# LED_aluminum.net
KiCad netlist of a schematic drawn in Altium Designer
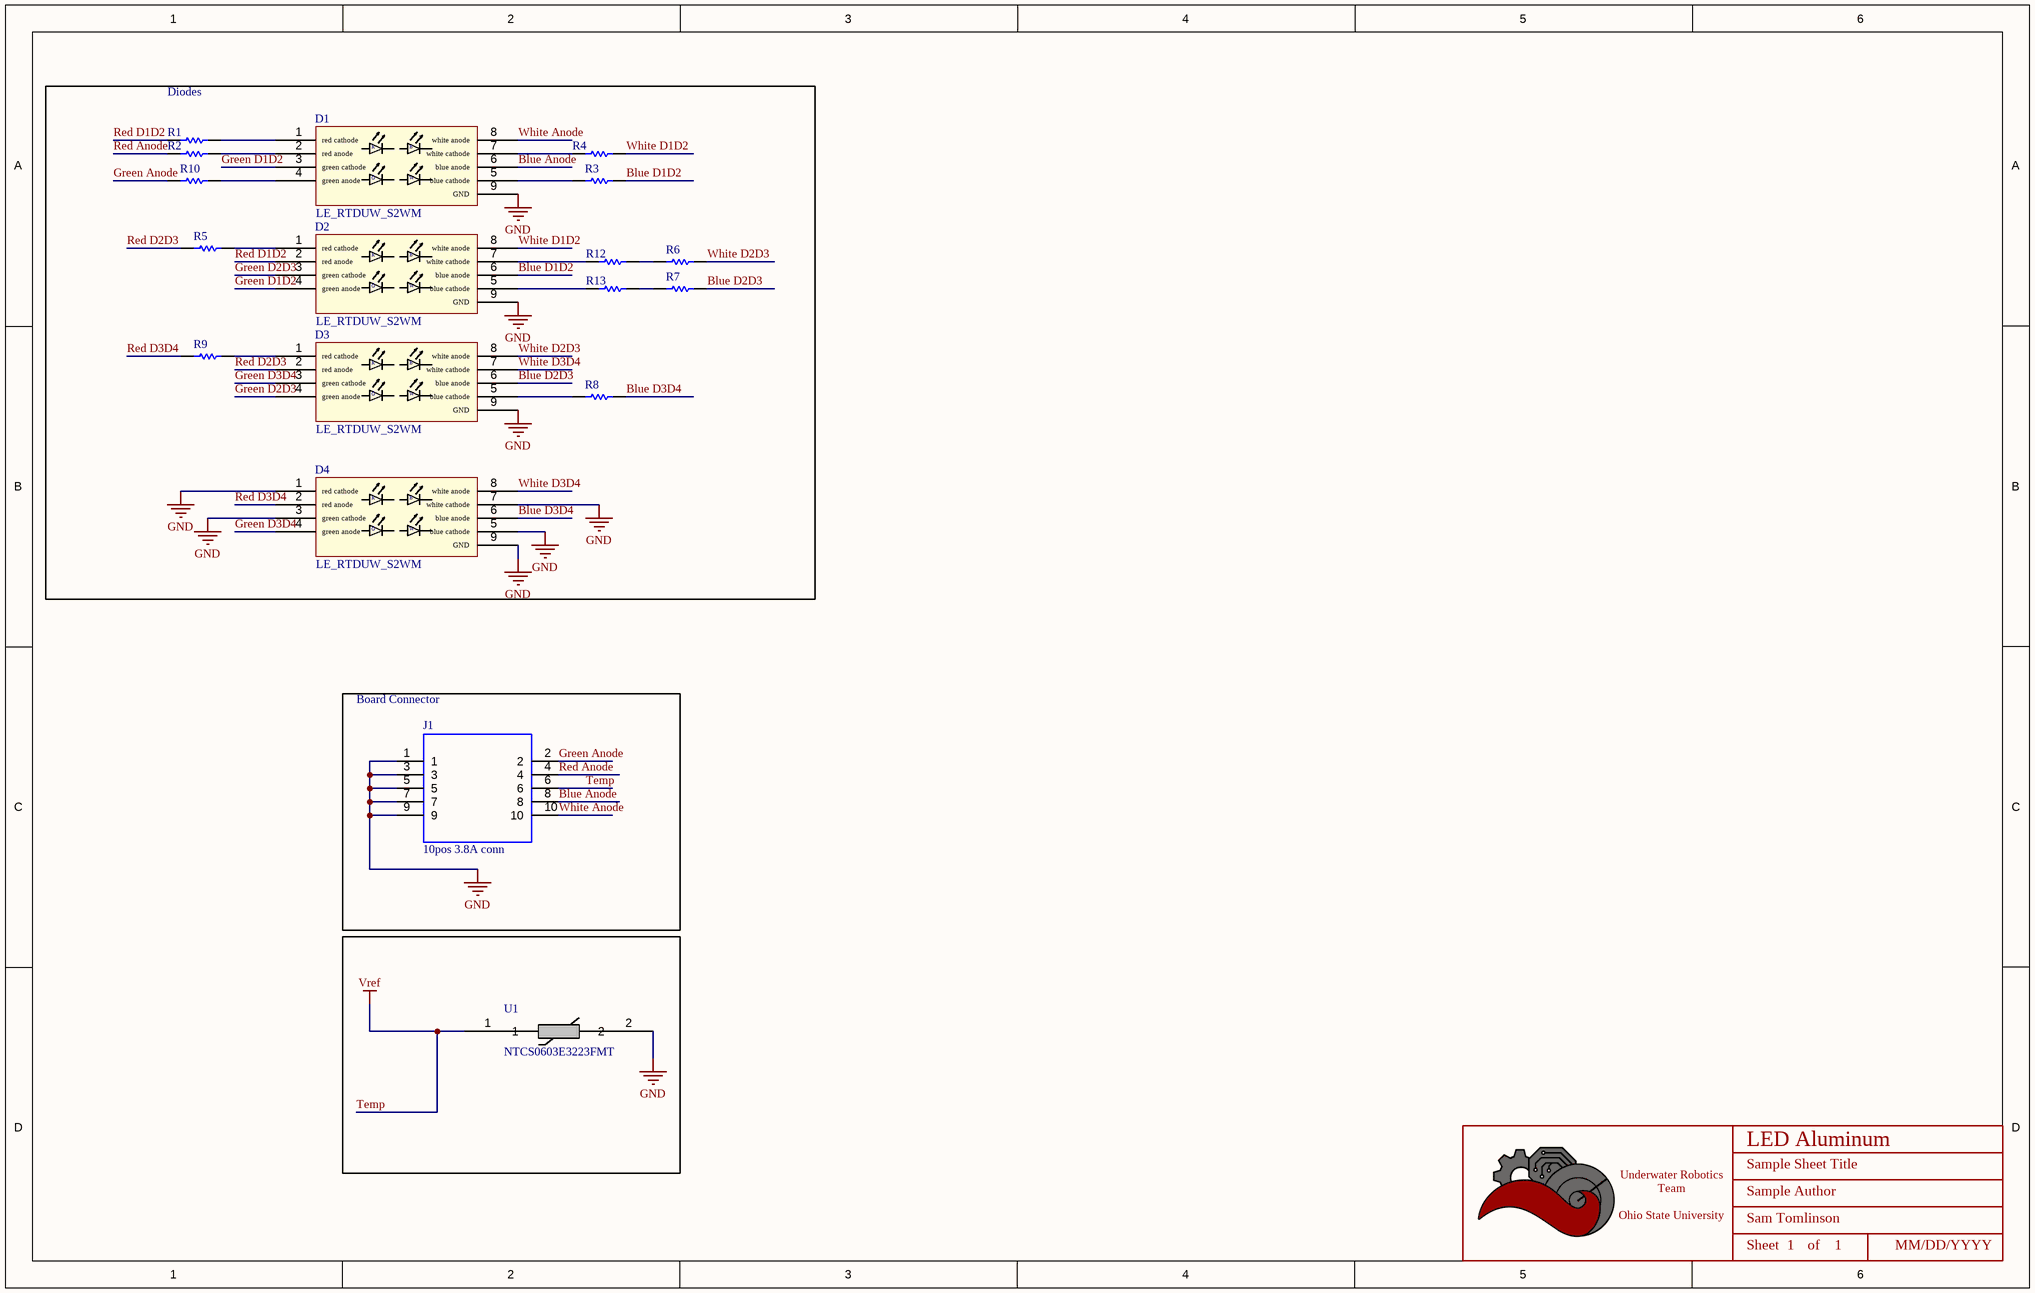
[diagram p0: LED_aluminum.SchDoc]

(export (version "E")
  (design (tool "Eeschema 10.0.6"))
  (components
    (comp (ref "*")
      (value "Title_Block")
      (footprint "LOGO")
      (description "UWRT Schematic Title Block Template\r\n\r\nCreated June 2021, Dylan Trainor")
      (libsource (lib "UWRT") (part "Title_Block"))
    )
    (comp (ref "D1")
      (value "LE_RTDUW_S2WM")
      (footprint "LE_RTDUW_S2WM")
      (description "LED OSTAR RGBW 625/527/453NM SMD")
      (libsource (lib "Diodes") (part "LE_RTDUW_S2WM"))
    )
    (comp (ref "D2")
      (value "LE_RTDUW_S2WM")
      (footprint "LE_RTDUW_S2WM")
      (description "LED OSTAR RGBW 625/527/453NM SMD")
      (libsource (lib "Diodes") (part "LE_RTDUW_S2WM"))
    )
    (comp (ref "D3")
      (value "LE_RTDUW_S2WM")
      (footprint "LE_RTDUW_S2WM")
      (description "LED OSTAR RGBW 625/527/453NM SMD")
      (libsource (lib "Diodes") (part "LE_RTDUW_S2WM"))
    )
    (comp (ref "D4")
      (value "LE_RTDUW_S2WM")
      (footprint "LE_RTDUW_S2WM")
      (description "LED OSTAR RGBW 625/527/453NM SMD")
      (libsource (lib "Diodes") (part "LE_RTDUW_S2WM"))
    )
    (comp (ref "J1")
      (value "10pos 3.8A conn")
      (footprint "SAMTEC-LS2-105-01-X-D-RA2")
      (description "10 Position Connector Self Mating, Non-Gendered, Hermaphroditic Through Hole, Right Angle Gold")
      (fields (field (name "MP") "SAMTEC-LS2-105-01-X-D-RA2"))
      (libsource (lib "Connectors") (part "SAMTEC-LS2-105-01-X-D-RA2"))
    )
    (comp (ref "R1")
      (value "Jumper 2512(6432)")
      (footprint "RESC2512(6432)_L")
      (description "Jumper 2512 (6432 Metric)")
      (fields (field (name "TOLERANCE") "None"))
      (libsource (lib "Altium Content Vault") (part "RES"))
    )
    (comp (ref "R2")
      (value "ERJ-8GEY0R00V")
      (footprint "RESC3216X70X50NL05T20")
      (fields (field (name "MANUFACTURER") "Panasonic"))
      (libsource (lib "Altium Content Vault") (part "RES"))
    )
    (comp (ref "R3")
      (value "Jumper 2512(6432)")
      (footprint "RESC2512(6432)_L")
      (description "Jumper 2512 (6432 Metric)")
      (fields (field (name "TOLERANCE") "None"))
      (libsource (lib "Altium Content Vault") (part "RES"))
    )
    (comp (ref "R4")
      (value "ERJ-8GEY0R00V")
      (footprint "RESC3216X70X50NL05T20")
      (fields (field (name "MANUFACTURER") "Panasonic"))
      (libsource (lib "Altium Content Vault") (part "RES"))
    )
    (comp (ref "R5")
      (value "Jumper 2512(6432)")
      (footprint "RESC2512(6432)_L")
      (description "Jumper 2512 (6432 Metric)")
      (fields (field (name "TOLERANCE") "None"))
      (libsource (lib "Altium Content Vault") (part "RES"))
    )
    (comp (ref "R6")
      (value "Jumper 2512(6432)")
      (footprint "RESC2512(6432)_L")
      (description "Jumper 2512 (6432 Metric)")
      (fields (field (name "TOLERANCE") "None"))
      (libsource (lib "Altium Content Vault") (part "RES"))
    )
    (comp (ref "R7")
      (value "ERJ-8GEY0R00V")
      (footprint "RESC3216X70X50NL05T20")
      (fields (field (name "MANUFACTURER") "Panasonic"))
      (libsource (lib "Altium Content Vault") (part "RES"))
    )
    (comp (ref "R8")
      (value "ERJ-8GEY0R00V")
      (footprint "RESC3216X70X50NL05T20")
      (fields (field (name "MANUFACTURER") "Panasonic"))
      (libsource (lib "Altium Content Vault") (part "RES"))
    )
    (comp (ref "R9")
      (value "ERJ-8GEY0R00V")
      (footprint "RESC3216X70X50NL05T20")
      (fields (field (name "MANUFACTURER") "Panasonic"))
      (libsource (lib "Altium Content Vault") (part "RES"))
    )
    (comp (ref "R10")
      (value "ERJ-8GEY0R00V")
      (footprint "RESC3216X70X50NL05T20")
      (fields (field (name "MANUFACTURER") "Panasonic"))
      (libsource (lib "Altium Content Vault") (part "RES"))
    )
    (comp (ref "R12")
      (value "ERJ-8GEY0R00V")
      (footprint "RESC3216X70X50NL05T20")
      (fields (field (name "MANUFACTURER") "Panasonic"))
      (libsource (lib "Altium Content Vault") (part "RES"))
    )
    (comp (ref "R13")
      (value "Jumper 2512(6432)")
      (footprint "RESC2512(6432)_L")
      (description "Jumper 2512 (6432 Metric)")
      (fields (field (name "TOLERANCE") "None"))
      (libsource (lib "Altium Content Vault") (part "RES"))
    )
    (comp (ref "U1")
      (value "NTCS0603E3223FMT")
      (footprint "NTCS0603_VIS")
      (fields (field (name "TOLERANCE") "1%"))
      (libsource (lib "Altium Content Vault") (part "NTCS0603E3223FMT"))
    )
  )
  (nets
    (net (code "1") (name "/Blue Anode") (class "Default")
      (node (ref "D1") (pin "6") (pinfunction "blue_anode_6") (pintype "passive"))
      (node (ref "J1") (pin "8") (pinfunction "8_8") (pintype "passive"))
    )
    (net (code "2") (name "/Blue D1D2") (class "Default")
      (node (ref "D2") (pin "6") (pinfunction "blue_anode_6") (pintype "passive"))
      (node (ref "R3") (pin "2") (pinfunction "2_2") (pintype "passive"))
    )
    (net (code "3") (name "/Blue D2D3") (class "Default")
      (node (ref "D3") (pin "6") (pinfunction "blue_anode_6") (pintype "passive"))
      (node (ref "R7") (pin "2") (pinfunction "2_2") (pintype "passive"))
    )
    (net (code "4") (name "/Blue D3D4") (class "Default")
      (node (ref "D4") (pin "6") (pinfunction "blue_anode_6") (pintype "passive"))
      (node (ref "R8") (pin "2") (pinfunction "2_2") (pintype "passive"))
    )
    (net (code "5") (name "/Green Anode") (class "Default")
      (node (ref "J1") (pin "2") (pinfunction "2_2") (pintype "passive"))
      (node (ref "R10") (pin "1") (pinfunction "1_1") (pintype "passive"))
    )
    (net (code "6") (name "/Green D1D2") (class "Default")
      (node (ref "D1") (pin "3") (pinfunction "green_cathode_3") (pintype "passive"))
      (node (ref "D2") (pin "4") (pinfunction "green_anode_4") (pintype "passive"))
    )
    (net (code "7") (name "/Green D2D3") (class "Default")
      (node (ref "D2") (pin "3") (pinfunction "green_cathode_3") (pintype "passive"))
      (node (ref "D3") (pin "4") (pinfunction "green_anode_4") (pintype "passive"))
    )
    (net (code "8") (name "/Green D3D4") (class "Default")
      (node (ref "D3") (pin "3") (pinfunction "green_cathode_3") (pintype "passive"))
      (node (ref "D4") (pin "4") (pinfunction "green_anode_4") (pintype "passive"))
    )
    (net (code "9") (name "/Red Anode") (class "Default")
      (node (ref "J1") (pin "4") (pinfunction "4_4") (pintype "passive"))
      (node (ref "R2") (pin "1") (pinfunction "1_1") (pintype "passive"))
    )
    (net (code "10") (name "/Red D1D2") (class "Default")
      (node (ref "D2") (pin "2") (pinfunction "red_anode_2") (pintype "passive"))
      (node (ref "R1") (pin "1") (pinfunction "1_1") (pintype "passive"))
    )
    (net (code "11") (name "/Red D2D3") (class "Default")
      (node (ref "D3") (pin "2") (pinfunction "red_anode_2") (pintype "passive"))
      (node (ref "R5") (pin "1") (pinfunction "1_1") (pintype "passive"))
    )
    (net (code "12") (name "/Red D3D4") (class "Default")
      (node (ref "D4") (pin "2") (pinfunction "red_anode_2") (pintype "passive"))
      (node (ref "R9") (pin "1") (pinfunction "1_1") (pintype "passive"))
    )
    (net (code "13") (name "/White Anode") (class "Default")
      (node (ref "D1") (pin "8") (pinfunction "white_anode_8") (pintype "passive"))
      (node (ref "J1") (pin "10") (pinfunction "10_10") (pintype "passive"))
    )
    (net (code "14") (name "/White D1D2") (class "Default")
      (node (ref "D2") (pin "8") (pinfunction "white_anode_8") (pintype "passive"))
      (node (ref "R4") (pin "2") (pinfunction "2_2") (pintype "passive"))
    )
    (net (code "15") (name "/White D2D3") (class "Default")
      (node (ref "D3") (pin "8") (pinfunction "white_anode_8") (pintype "passive"))
      (node (ref "R6") (pin "2") (pinfunction "2_2") (pintype "passive"))
    )
    (net (code "16") (name "/White D3D4") (class "Default")
      (node (ref "D3") (pin "7") (pinfunction "white_cathode_7") (pintype "passive"))
      (node (ref "D4") (pin "8") (pinfunction "white_anode_8") (pintype "passive"))
    )
    (net (code "17") (name "GND") (class "Default")
      (node (ref "D1") (pin "9") (pinfunction "GND_9") (pintype "passive"))
      (node (ref "D2") (pin "9") (pinfunction "GND_9") (pintype "passive"))
      (node (ref "D3") (pin "9") (pinfunction "GND_9") (pintype "passive"))
      (node (ref "D4") (pin "1") (pinfunction "red_cathode_1") (pintype "passive"))
      (node (ref "D4") (pin "3") (pinfunction "green_cathode_3") (pintype "passive"))
      (node (ref "D4") (pin "5") (pinfunction "blue_cathode_5") (pintype "passive"))
      (node (ref "D4") (pin "7") (pinfunction "white_cathode_7") (pintype "passive"))
      (node (ref "D4") (pin "9") (pinfunction "GND_9") (pintype "passive"))
      (node (ref "J1") (pin "1") (pinfunction "1_1") (pintype "passive"))
      (node (ref "J1") (pin "3") (pinfunction "3_3") (pintype "passive"))
      (node (ref "J1") (pin "5") (pinfunction "5_5") (pintype "passive"))
      (node (ref "J1") (pin "7") (pinfunction "7_7") (pintype "passive"))
      (node (ref "J1") (pin "9") (pinfunction "9_9") (pintype "passive"))
      (node (ref "U1") (pin "2") (pinfunction "2_2") (pintype "passive"))
    )
    (net (code "18") (name "Net-(D1-blue_cathode)") (class "Default")
      (node (ref "D1") (pin "5") (pinfunction "blue_cathode_5") (pintype "passive"))
      (node (ref "R3") (pin "1") (pinfunction "1_1") (pintype "passive"))
    )
    (net (code "19") (name "Net-(D1-green_anode)") (class "Default")
      (node (ref "D1") (pin "4") (pinfunction "green_anode_4") (pintype "passive"))
      (node (ref "R10") (pin "2") (pinfunction "2_2") (pintype "passive"))
    )
    (net (code "20") (name "Net-(D1-red_anode)") (class "Default")
      (node (ref "D1") (pin "2") (pinfunction "red_anode_2") (pintype "passive"))
      (node (ref "R2") (pin "2") (pinfunction "2_2") (pintype "passive"))
    )
    (net (code "21") (name "Net-(D1-red_cathode)") (class "Default")
      (node (ref "D1") (pin "1") (pinfunction "red_cathode_1") (pintype "passive"))
      (node (ref "R1") (pin "2") (pinfunction "2_2") (pintype "passive"))
    )
    (net (code "22") (name "Net-(D1-white_cathode)") (class "Default")
      (node (ref "D1") (pin "7") (pinfunction "white_cathode_7") (pintype "passive"))
      (node (ref "R4") (pin "1") (pinfunction "1_1") (pintype "passive"))
    )
    (net (code "23") (name "Net-(D2-blue_cathode)") (class "Default")
      (node (ref "D2") (pin "5") (pinfunction "blue_cathode_5") (pintype "passive"))
      (node (ref "R13") (pin "1") (pinfunction "1_1") (pintype "passive"))
    )
    (net (code "24") (name "Net-(D2-red_cathode)") (class "Default")
      (node (ref "D2") (pin "1") (pinfunction "red_cathode_1") (pintype "passive"))
      (node (ref "R5") (pin "2") (pinfunction "2_2") (pintype "passive"))
    )
    (net (code "25") (name "Net-(D2-white_cathode)") (class "Default")
      (node (ref "D2") (pin "7") (pinfunction "white_cathode_7") (pintype "passive"))
      (node (ref "R12") (pin "1") (pinfunction "1_1") (pintype "passive"))
    )
    (net (code "26") (name "Net-(D3-blue_cathode)") (class "Default")
      (node (ref "D3") (pin "5") (pinfunction "blue_cathode_5") (pintype "passive"))
      (node (ref "R8") (pin "1") (pinfunction "1_1") (pintype "passive"))
    )
    (net (code "27") (name "Net-(D3-red_cathode)") (class "Default")
      (node (ref "D3") (pin "1") (pinfunction "red_cathode_1") (pintype "passive"))
      (node (ref "R9") (pin "2") (pinfunction "2_2") (pintype "passive"))
    )
    (net (code "28") (name "Net-(R12-Pad2)") (class "Default")
      (node (ref "R12") (pin "2") (pinfunction "2_2") (pintype "passive"))
      (node (ref "R6") (pin "1") (pinfunction "1_1") (pintype "passive"))
    )
    (net (code "29") (name "Net-(R13-Pad2)") (class "Default")
      (node (ref "R13") (pin "2") (pinfunction "2_2") (pintype "passive"))
      (node (ref "R7") (pin "1") (pinfunction "1_1") (pintype "passive"))
    )
    (net (code "30") (name "Vref") (class "Default")
      (node (ref "J1") (pin "6") (pinfunction "6_6") (pintype "passive"))
      (node (ref "U1") (pin "1") (pinfunction "1_1") (pintype "passive"))
    )
  )
)
